# debouncer_4x.net
KiCad netlist of a schematic drawn in EAGLE
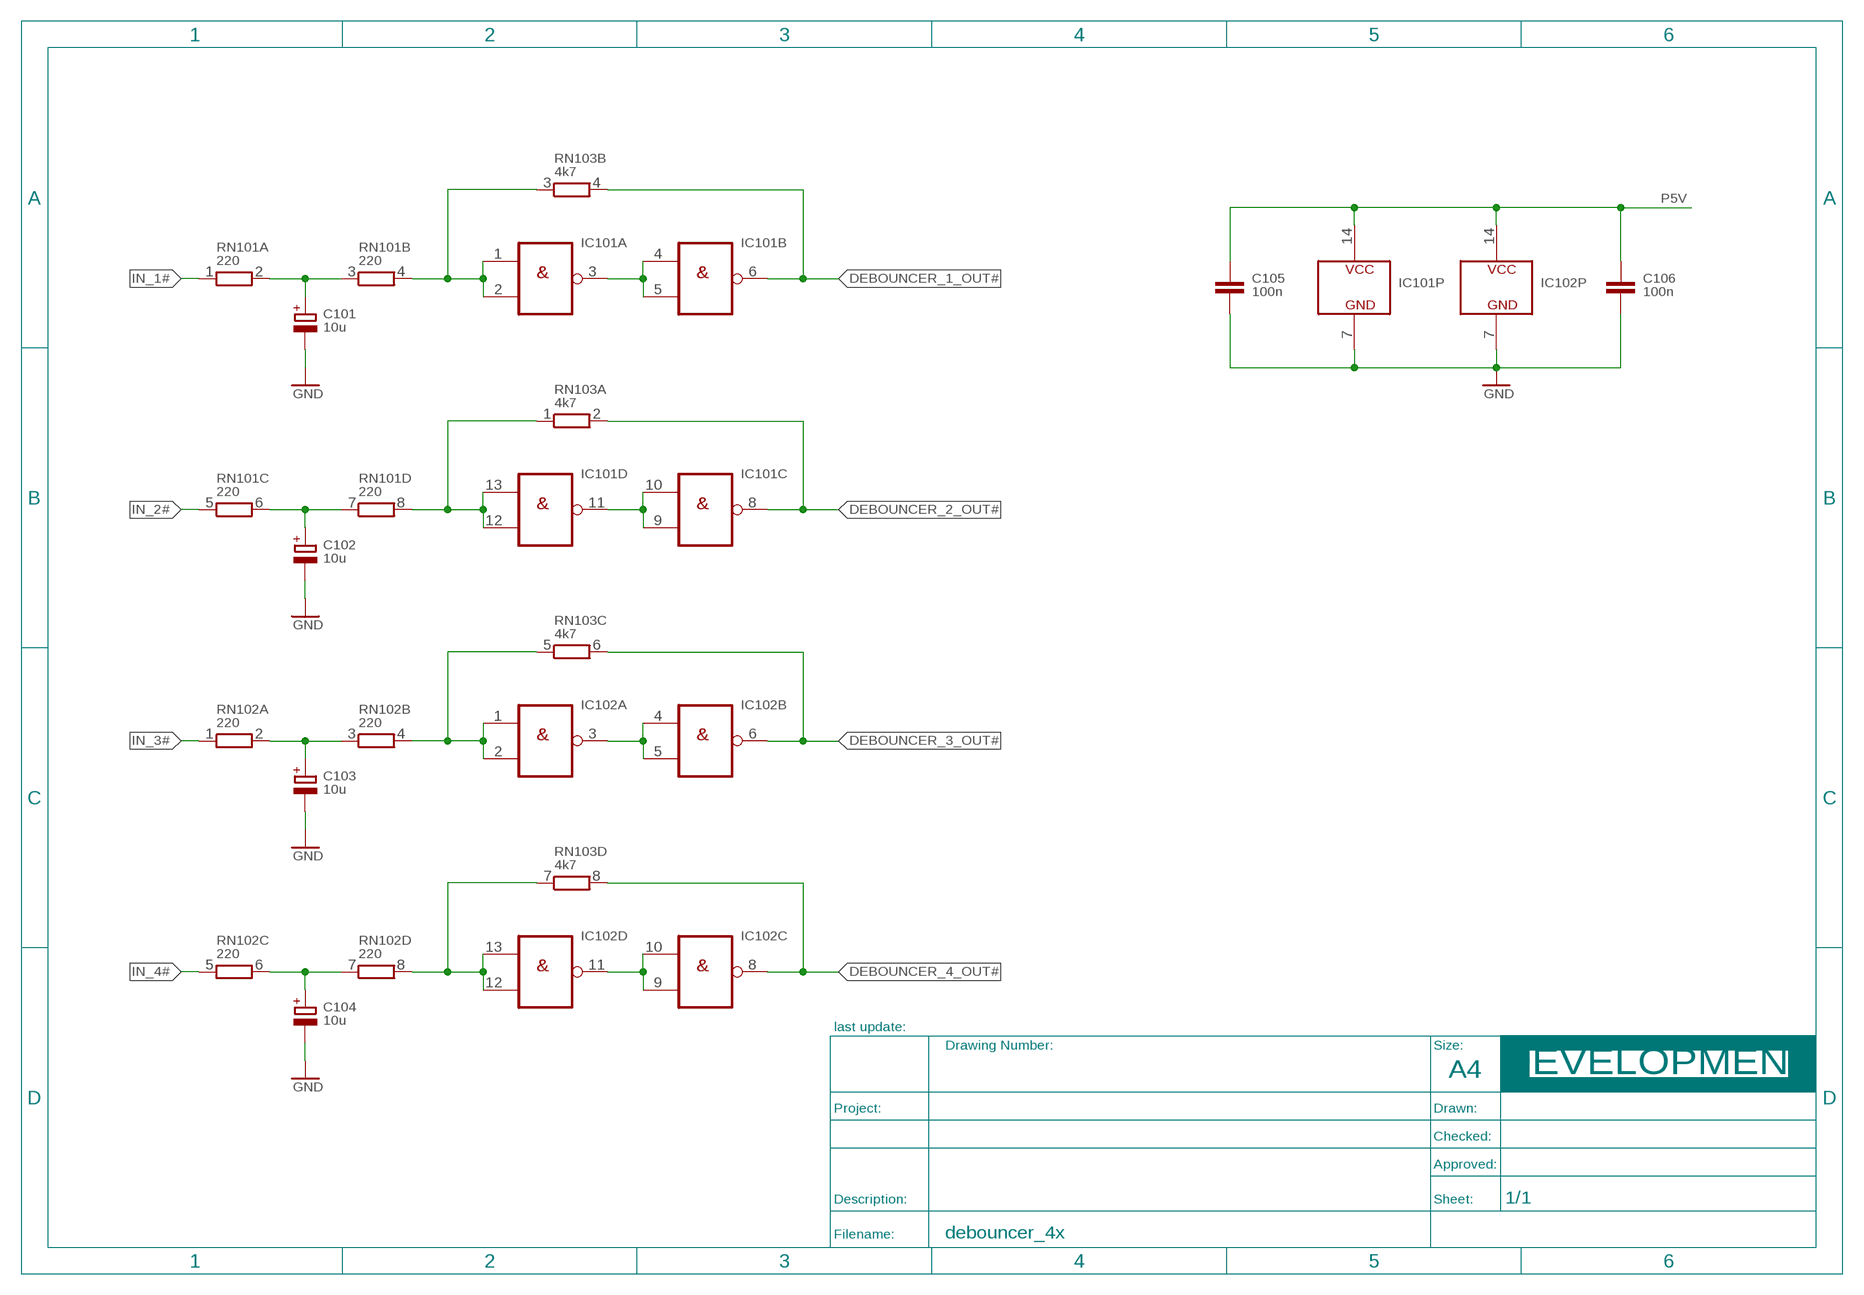
[diagram p0: schematic, sheet 1]

(export (version "E")
  (design (tool "Eeschema 10.0.6"))
  (components
    (comp (ref "C101")
      (value "10u")
      (footprint "eagle-import:T_RADIAL_5MM_GRID_2.54MM")
      (fields (field (name "PART_CODE_BEL") "C_PAC_T_RADIAL_5mm_GRID_2.54mm_VAL_10u_Vmax_35V"))
      (libsource (lib "eagle-import") (part "C_POL_EU_T_RAD5_GRID_2.54"))
    )
    (comp (ref "C102")
      (value "10u")
      (footprint "eagle-import:T_RADIAL_5MM_GRID_2.54MM")
      (fields (field (name "PART_CODE_BEL") "C_PAC_T_RADIAL_5mm_GRID_2.54mm_VAL_10u_Vmax_35V"))
      (libsource (lib "eagle-import") (part "C_POL_EU_T_RAD5_GRID_2.54"))
    )
    (comp (ref "C103")
      (value "10u")
      (footprint "eagle-import:T_RADIAL_5MM_GRID_2.54MM")
      (fields (field (name "PART_CODE_BEL") "C_PAC_T_RADIAL_5mm_GRID_2.54mm_VAL_10u_Vmax_35V"))
      (libsource (lib "eagle-import") (part "C_POL_EU_T_RAD5_GRID_2.54"))
    )
    (comp (ref "C104")
      (value "10u")
      (footprint "eagle-import:T_RADIAL_5MM_GRID_2.54MM")
      (fields (field (name "PART_CODE_BEL") "C_PAC_T_RADIAL_5mm_GRID_2.54mm_VAL_10u_Vmax_35V"))
      (libsource (lib "eagle-import") (part "C_POL_EU_T_RAD5_GRID_2.54"))
    )
    (comp (ref "C105")
      (value "100n")
      (footprint "eagle-import:S_0805")
      (fields (field (name "PART_CODE_BEL") "C_PAC_S_0805_VAL_100n"))
      (libsource (lib "eagle-import") (part "C_EU_S_0805"))
    )
    (comp (ref "C106")
      (value "100n")
      (footprint "eagle-import:S_0805")
      (fields (field (name "PART_CODE_BEL") "C_PAC_S_0805_VAL_100n"))
      (libsource (lib "eagle-import") (part "C_EU_S_0805"))
    )
    (comp (ref "IC101")
      (value "7400N")
      (footprint "eagle-import:T_NDIP14")
      (libsource (lib "eagle-import") (part "7400N"))
    )
    (comp (ref "IC102")
      (value "7400N")
      (footprint "eagle-import:T_NDIP14")
      (libsource (lib "eagle-import") (part "7400N"))
    )
    (comp (ref "RN101")
      (value "220")
      (footprint "eagle-import:T_SIL8")
      (libsource (lib "eagle-import") (part "R_EU_ARRAY_4"))
    )
    (comp (ref "RN102")
      (value "220")
      (footprint "eagle-import:T_SIL8")
      (libsource (lib "eagle-import") (part "R_EU_ARRAY_4"))
    )
    (comp (ref "RN103")
      (value "4k7")
      (footprint "eagle-import:T_SIL8")
      (fields (field (name "PART_CODE_BEL") "RN_PAC_T_SIL8_VAL_4k7"))
      (libsource (lib "eagle-import") (part "R_EU_ARRAY_4"))
    )
  )
  (nets
    (net (code "1") (name "/P5V") (class "Default")
      (node (ref "C105") (pin "1") (pinfunction "1_1") (pintype "passive"))
      (node (ref "C106") (pin "1") (pinfunction "1_1") (pintype "passive"))
      (node (ref "IC101") (pin "14") (pinfunction "VCC_14") (pintype "power_in"))
      (node (ref "IC102") (pin "14") (pinfunction "VCC_14") (pintype "power_in"))
    )
    (net (code "2") (name "DEBOUNCER_1_OUT#") (class "Default")
      (node (ref "IC101") (pin "6") (pinfunction "O_6") (pintype "output"))
      (node (ref "RN103") (pin "4") (pinfunction "2_4") (pintype "passive"))
    )
    (net (code "3") (name "DEBOUNCER_2_OUT#") (class "Default")
      (node (ref "IC101") (pin "8") (pinfunction "O_8") (pintype "output"))
      (node (ref "RN103") (pin "2") (pinfunction "2_2") (pintype "passive"))
    )
    (net (code "4") (name "DEBOUNCER_3_OUT#") (class "Default")
      (node (ref "IC102") (pin "6") (pinfunction "O_6") (pintype "output"))
      (node (ref "RN103") (pin "6") (pinfunction "2_6") (pintype "passive"))
    )
    (net (code "5") (name "DEBOUNCER_4_OUT#") (class "Default")
      (node (ref "IC102") (pin "8") (pinfunction "O_8") (pintype "output"))
      (node (ref "RN103") (pin "8") (pinfunction "2_8") (pintype "passive"))
    )
    (net (code "6") (name "GND") (class "Default")
      (node (ref "C101") (pin "-") (pinfunction "-_-") (pintype "passive"))
      (node (ref "C102") (pin "-") (pinfunction "-_-") (pintype "passive"))
      (node (ref "C103") (pin "-") (pinfunction "-_-") (pintype "passive"))
      (node (ref "C104") (pin "-") (pinfunction "-_-") (pintype "passive"))
      (node (ref "C105") (pin "2") (pinfunction "2_2") (pintype "passive"))
      (node (ref "C106") (pin "2") (pinfunction "2_2") (pintype "passive"))
      (node (ref "IC101") (pin "7") (pinfunction "GND_7") (pintype "power_in"))
      (node (ref "IC102") (pin "7") (pinfunction "GND_7") (pintype "power_in"))
    )
    (net (code "7") (name "IN_1#") (class "Default")
      (node (ref "RN101") (pin "1") (pinfunction "1_1") (pintype "passive"))
    )
    (net (code "8") (name "IN_2#") (class "Default")
      (node (ref "RN101") (pin "5") (pinfunction "1_5") (pintype "passive"))
    )
    (net (code "9") (name "IN_3#") (class "Default")
      (node (ref "RN102") (pin "1") (pinfunction "1_1") (pintype "passive"))
    )
    (net (code "10") (name "IN_4#") (class "Default")
      (node (ref "RN102") (pin "5") (pinfunction "1_5") (pintype "passive"))
    )
    (net (code "11") (name "Net-(IC101A-I0)") (class "Default")
      (node (ref "IC101") (pin "1") (pinfunction "I0_1") (pintype "input"))
      (node (ref "IC101") (pin "2") (pinfunction "I1_2") (pintype "input"))
      (node (ref "RN101") (pin "4") (pinfunction "2_4") (pintype "passive"))
      (node (ref "RN103") (pin "3") (pinfunction "1_3") (pintype "passive"))
    )
    (net (code "12") (name "Net-(IC101A-O)") (class "Default")
      (node (ref "IC101") (pin "3") (pinfunction "O_3") (pintype "output"))
      (node (ref "IC101") (pin "4") (pinfunction "I0_4") (pintype "input"))
      (node (ref "IC101") (pin "5") (pinfunction "I1_5") (pintype "input"))
    )
    (net (code "13") (name "Net-(IC101C-I0)") (class "Default")
      (node (ref "IC101") (pin "10") (pinfunction "I0_10") (pintype "input"))
      (node (ref "IC101") (pin "11") (pinfunction "O_11") (pintype "output"))
      (node (ref "IC101") (pin "9") (pinfunction "I1_9") (pintype "input"))
    )
    (net (code "14") (name "Net-(IC101D-I0)") (class "Default")
      (node (ref "IC101") (pin "12") (pinfunction "I1_12") (pintype "input"))
      (node (ref "IC101") (pin "13") (pinfunction "I0_13") (pintype "input"))
      (node (ref "RN101") (pin "8") (pinfunction "2_8") (pintype "passive"))
      (node (ref "RN103") (pin "1") (pinfunction "1_1") (pintype "passive"))
    )
    (net (code "15") (name "Net-(IC102A-I0)") (class "Default")
      (node (ref "IC102") (pin "1") (pinfunction "I0_1") (pintype "input"))
      (node (ref "IC102") (pin "2") (pinfunction "I1_2") (pintype "input"))
      (node (ref "RN102") (pin "4") (pinfunction "2_4") (pintype "passive"))
      (node (ref "RN103") (pin "5") (pinfunction "1_5") (pintype "passive"))
    )
    (net (code "16") (name "Net-(IC102A-O)") (class "Default")
      (node (ref "IC102") (pin "3") (pinfunction "O_3") (pintype "output"))
      (node (ref "IC102") (pin "4") (pinfunction "I0_4") (pintype "input"))
      (node (ref "IC102") (pin "5") (pinfunction "I1_5") (pintype "input"))
    )
    (net (code "17") (name "Net-(IC102C-I0)") (class "Default")
      (node (ref "IC102") (pin "10") (pinfunction "I0_10") (pintype "input"))
      (node (ref "IC102") (pin "11") (pinfunction "O_11") (pintype "output"))
      (node (ref "IC102") (pin "9") (pinfunction "I1_9") (pintype "input"))
    )
    (net (code "18") (name "Net-(IC102D-I0)") (class "Default")
      (node (ref "IC102") (pin "12") (pinfunction "I1_12") (pintype "input"))
      (node (ref "IC102") (pin "13") (pinfunction "I0_13") (pintype "input"))
      (node (ref "RN102") (pin "8") (pinfunction "2_8") (pintype "passive"))
      (node (ref "RN103") (pin "7") (pinfunction "1_7") (pintype "passive"))
    )
    (net (code "19") (name "Net-(RN101B-1)") (class "Default")
      (node (ref "C101") (pin "+") (pinfunction "+_+") (pintype "passive"))
      (node (ref "RN101") (pin "2") (pinfunction "2_2") (pintype "passive"))
      (node (ref "RN101") (pin "3") (pinfunction "1_3") (pintype "passive"))
    )
    (net (code "20") (name "Net-(RN101C-2)") (class "Default")
      (node (ref "C102") (pin "+") (pinfunction "+_+") (pintype "passive"))
      (node (ref "RN101") (pin "6") (pinfunction "2_6") (pintype "passive"))
      (node (ref "RN101") (pin "7") (pinfunction "1_7") (pintype "passive"))
    )
    (net (code "21") (name "Net-(RN102B-1)") (class "Default")
      (node (ref "C103") (pin "+") (pinfunction "+_+") (pintype "passive"))
      (node (ref "RN102") (pin "2") (pinfunction "2_2") (pintype "passive"))
      (node (ref "RN102") (pin "3") (pinfunction "1_3") (pintype "passive"))
    )
    (net (code "22") (name "Net-(RN102C-2)") (class "Default")
      (node (ref "C104") (pin "+") (pinfunction "+_+") (pintype "passive"))
      (node (ref "RN102") (pin "6") (pinfunction "2_6") (pintype "passive"))
      (node (ref "RN102") (pin "7") (pinfunction "1_7") (pintype "passive"))
    )
  )
)
